# 12V_Supply.net
KiCad netlist of a schematic drawn in Altium Designer
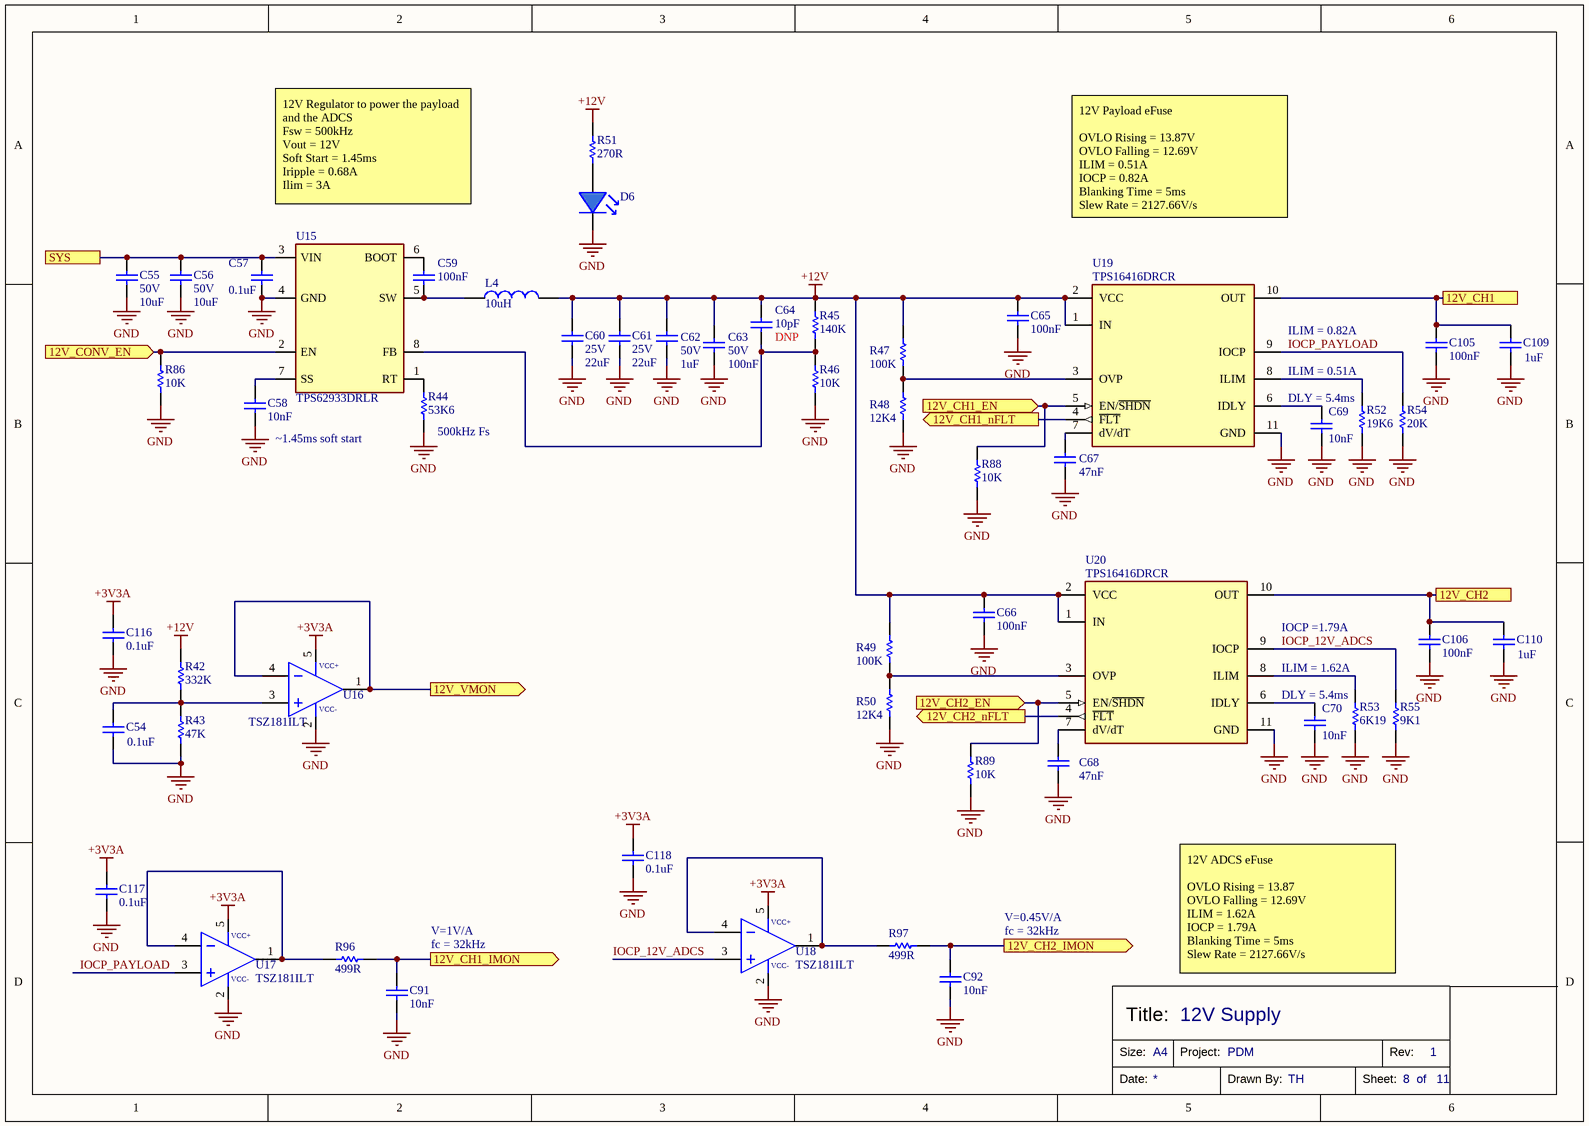
[diagram p0: 12V_Supply.SchDoc]

(export (version "E")
  (design (tool "Eeschema 10.0.6"))
  (components
    (comp (ref "C54")
      (value "CL21B104KACNNNC")
      (footprint "CAPC0805X060")
      (description "0.1uF ±10% 25V Ceramic Capacitor X7R 0805 (2012 Metric)")
      (fields
        (field (name "DISTRIBUTOR PART NUMBER") "1276-1099-1-ND")
        (field (name "TOLERANCE") "10%")
        (field (name "CAPACITANCE") "0.1uF")
      )
      (libsource (lib "Ahristi_Library") (part "CL21B104KACNNNC"))
    )
    (comp (ref "C55")
      (value "CL32B106KBJNNNE")
      (footprint "CAPC1210X090")
      (description "10 µF ±10% 50V Ceramic Capacitor X7R 1210 (3225 Metric)")
      (fields
        (field (name "DISTRIBUTOR PART NUMBER") "1276-3387-1-ND")
        (field (name "TOLERANCE") "10%")
        (field (name "VOLTAGE RATING") "50V")
        (field (name "CAPACITANCE") "10uF")
      )
      (libsource (lib "Ahristi_Library") (part "CL32B106KBJNNNE"))
    )
    (comp (ref "C56")
      (value "CL32B106KBJNNNE")
      (footprint "CAPC1210X090")
      (description "10 µF ±10% 50V Ceramic Capacitor X7R 1210 (3225 Metric)")
      (fields
        (field (name "DISTRIBUTOR PART NUMBER") "1276-3387-1-ND")
        (field (name "TOLERANCE") "10%")
        (field (name "VOLTAGE RATING") "50V")
        (field (name "CAPACITANCE") "10uF")
      )
      (libsource (lib "Ahristi_Library") (part "CL32B106KBJNNNE"))
    )
    (comp (ref "C57")
      (value "CL05B104KB5NNNC")
      (footprint "CAPC0402X020")
      (description "0.1 µF ±10% 50V Ceramic Capacitor X7R 0402 (1005 Metric)")
      (fields
        (field (name "TOLERANCE") "10%")
        (field (name "DISTRIBUTOR PART NUMBER") "1276-CL05B104KB5NNNCCT-ND")
        (field (name "CAPACITANCE") "0.1uF")
      )
      (libsource (lib "Ahristi_Library") (part "CL05B104KB5NNNC"))
    )
    (comp (ref "C58")
      (value "CL21B103KBANNNC")
      (footprint "CAPC0805X060")
      (description "10nF ±10% 50V Ceramic Capacitor X7R 0805 (2012 Metric)")
      (fields
        (field (name "DISTRIBUTOR PART NUMBER") "1276-1015-1-ND")
        (field (name "TOLERANCE") "10%")
        (field (name "CAPACITANCE") "10nF")
      )
      (libsource (lib "Ahristi_Library") (part "CL21B103KBANNNC"))
    )
    (comp (ref "C59")
      (value "C0603C104K5RACTU")
      (footprint "CAPC0603X040")
      (description "0.1 µF ±10% 50V Ceramic Capacitor X7R 0603 (1608 Metric)")
      (fields
        (field (name "DISTRIBUTOR PART NUMBER") "399-C0603C104K5RACTUCT-ND")
        (field (name "TOLERANCE") "10%")
        (field (name "CAPACITANCE") "100nF")
      )
      (libsource (lib "Ahristi_Library") (part "C0603C104K5RACTU"))
    )
    (comp (ref "C60")
      (value "CL32B226KAJNNNE")
      (footprint "CAPC1210X090")
      (description "22 µF ±10% 25V Ceramic Capacitor X7R 1210 (3225 Metric)")
      (fields
        (field (name "DISTRIBUTOR PART NUMBER") "1276-3392-1-ND")
        (field (name "TOLERANCE") "10%")
        (field (name "VOLTAGE RATING") "25V")
        (field (name "CAPACITANCE") "22uF")
      )
      (libsource (lib "Ahristi_Library") (part "CL32B226KAJNNNE"))
    )
    (comp (ref "C61")
      (value "CL32B226KAJNNNE")
      (footprint "CAPC1210X090")
      (description "22 µF ±10% 25V Ceramic Capacitor X7R 1210 (3225 Metric)")
      (fields
        (field (name "DISTRIBUTOR PART NUMBER") "1276-3392-1-ND")
        (field (name "TOLERANCE") "10%")
        (field (name "VOLTAGE RATING") "25V")
        (field (name "CAPACITANCE") "22uF")
      )
      (libsource (lib "Ahristi_Library") (part "CL32B226KAJNNNE"))
    )
    (comp (ref "C62")
      (value "CL21B105KBFNNNE")
      (footprint "CAPC0805X060")
      (description "1uF 50V X7R ±10% 0805 Multilayer Ceramic Capacitors MLCC - SMD/SMT ROHS")
      (fields
        (field (name "DISTRIBUTOR PART NUMBER") "1276-1029-1-ND")
        (field (name "TOLERANCE") "10%")
        (field (name "VOLTAGE RATING") "50V")
        (field (name "CAPACITANCE") "1uF")
      )
      (libsource (lib "Ahristi_Library") (part "CL21B105KBFNNNE"))
    )
    (comp (ref "C63")
      (value "C0603C104K5RACTU")
      (footprint "CAPC0603X040")
      (description "0.1 µF ±10% 50V Ceramic Capacitor X7R 0603 (1608 Metric)")
      (fields
        (field (name "DISTRIBUTOR PART NUMBER") "399-C0603C104K5RACTUCT-ND")
        (field (name "TOLERANCE") "10%")
        (field (name "VOLTAGE RATING") "50V")
        (field (name "CAPACITANCE") "100nF")
      )
      (libsource (lib "Ahristi_Library") (part "C0603C104K5RACTU"))
    )
    (comp (ref "C64")
      (value "C0603C104K5RACTU")
      (footprint "CAPC0603X040")
      (description "10 pF ±5% 50V Ceramic Capacitor C0G, NP0 0603 (1608 Metric)")
      (fields
        (field (name "PART NUMBER") "C0603C100J5GACTU")
        (field (name "DISTRIBUTOR PART NUMBER") "399-C0603C100J5GACTUCT-ND")
        (field (name "CAPACITANCE") "10pF")
      )
      (libsource (lib "Ahristi_Library") (part "C0603C100J5GACTU"))
    )
    (comp (ref "C65")
      (value "C0603C104K5RACTU")
      (footprint "CAPC0603X040")
      (description "0.1 µF ±10% 50V Ceramic Capacitor X7R 0603 (1608 Metric)")
      (fields
        (field (name "DISTRIBUTOR PART NUMBER") "399-C0603C104K5RACTUCT-ND")
        (field (name "TOLERANCE") "10%")
        (field (name "CAPACITANCE") "100nF")
      )
      (libsource (lib "Ahristi_Library") (part "C0603C104K5RACTU"))
    )
    (comp (ref "C66")
      (value "C0603C104K5RACTU")
      (footprint "CAPC0603X040")
      (description "0.1 µF ±10% 50V Ceramic Capacitor X7R 0603 (1608 Metric)")
      (fields
        (field (name "DISTRIBUTOR PART NUMBER") "399-C0603C104K5RACTUCT-ND")
        (field (name "TOLERANCE") "10%")
        (field (name "CAPACITANCE") "100nF")
      )
      (libsource (lib "Ahristi_Library") (part "C0603C104K5RACTU"))
    )
    (comp (ref "C67")
      (value "CL21B473KBCNNNC")
      (footprint "CAPC0805X060")
      (description "0.047 µF ±10% 50V Ceramic Capacitor X7R 0805 (2012 Metric)")
      (fields
        (field (name "DISTRIBUTOR PART NUMBER") "1276-1250-1-ND")
        (field (name "TOLERANCE") "10%")
        (field (name "CAPACITANCE") "47nF")
      )
      (libsource (lib "Ahristi_Library") (part "CL21B473KBCNNNC"))
    )
    (comp (ref "C68")
      (value "CL21B473KBCNNNC")
      (footprint "CAPC0805X060")
      (description "0.047 µF ±10% 50V Ceramic Capacitor X7R 0805 (2012 Metric)")
      (fields
        (field (name "DISTRIBUTOR PART NUMBER") "1276-1250-1-ND")
        (field (name "TOLERANCE") "10%")
        (field (name "CAPACITANCE") "47nF")
      )
      (libsource (lib "Ahristi_Library") (part "CL21B473KBCNNNC"))
    )
    (comp (ref "C69")
      (value "CL21B103KBANNNC")
      (footprint "CAPC0805X060")
      (description "10nF ±10% 50V Ceramic Capacitor X7R 0805 (2012 Metric)")
      (fields
        (field (name "DISTRIBUTOR PART NUMBER") "1276-1015-1-ND")
        (field (name "TOLERANCE") "10%")
        (field (name "CAPACITANCE") "10nF")
      )
      (libsource (lib "Ahristi_Library") (part "CL21B103KBANNNC"))
    )
    (comp (ref "C70")
      (value "CL21B103KBANNNC")
      (footprint "CAPC0805X060")
      (description "10nF ±10% 50V Ceramic Capacitor X7R 0805 (2012 Metric)")
      (fields
        (field (name "DISTRIBUTOR PART NUMBER") "1276-1015-1-ND")
        (field (name "TOLERANCE") "10%")
        (field (name "CAPACITANCE") "10nF")
      )
      (libsource (lib "Ahristi_Library") (part "CL21B103KBANNNC"))
    )
    (comp (ref "C91")
      (value "CL21B103KBANNNC")
      (footprint "CAPC0805X060")
      (description "10nF ±10% 50V Ceramic Capacitor X7R 0805 (2012 Metric)")
      (fields
        (field (name "DISTRIBUTOR PART NUMBER") "1276-1015-1-ND")
        (field (name "TOLERANCE") "10%")
        (field (name "CAPACITANCE") "10nF")
      )
      (libsource (lib "Ahristi_Library") (part "CL21B103KBANNNC"))
    )
    (comp (ref "C92")
      (value "CL21B103KBANNNC")
      (footprint "CAPC0805X060")
      (description "10nF ±10% 50V Ceramic Capacitor X7R 0805 (2012 Metric)")
      (fields
        (field (name "DISTRIBUTOR PART NUMBER") "1276-1015-1-ND")
        (field (name "TOLERANCE") "10%")
        (field (name "CAPACITANCE") "10nF")
      )
      (libsource (lib "Ahristi_Library") (part "CL21B103KBANNNC"))
    )
    (comp (ref "C105")
      (value "C0603C104K5RACTU")
      (footprint "CAPC0603X040")
      (description "0.1 µF ±10% 50V Ceramic Capacitor X7R 0603 (1608 Metric)")
      (fields
        (field (name "DISTRIBUTOR PART NUMBER") "399-C0603C104K5RACTUCT-ND")
        (field (name "TOLERANCE") "10%")
        (field (name "CAPACITANCE") "100nF")
      )
      (libsource (lib "Ahristi_Library") (part "C0603C104K5RACTU"))
    )
    (comp (ref "C106")
      (value "C0603C104K5RACTU")
      (footprint "CAPC0603X040")
      (description "0.1 µF ±10% 50V Ceramic Capacitor X7R 0603 (1608 Metric)")
      (fields
        (field (name "DISTRIBUTOR PART NUMBER") "399-C0603C104K5RACTUCT-ND")
        (field (name "TOLERANCE") "10%")
        (field (name "CAPACITANCE") "100nF")
      )
      (libsource (lib "Ahristi_Library") (part "C0603C104K5RACTU"))
    )
    (comp (ref "C109")
      (value "CL21B105KAFNNNE")
      (footprint "CAPC0805X060")
      (description "1uF ±10% 25V Ceramic Capacitor X7R 0805 (2012 Metric)")
      (fields
        (field (name "DISTRIBUTOR PART NUMBER") "1276-1066-1-ND")
        (field (name "TOLERANCE") "10%")
        (field (name "CAPACITANCE") "1uF")
      )
      (libsource (lib "Ahristi_Library") (part "CL21B105KAFNNNE"))
    )
    (comp (ref "C110")
      (value "CL21B105KAFNNNE")
      (footprint "CAPC0805X060")
      (description "1uF ±10% 25V Ceramic Capacitor X7R 0805 (2012 Metric)")
      (fields
        (field (name "DISTRIBUTOR PART NUMBER") "1276-1066-1-ND")
        (field (name "TOLERANCE") "10%")
        (field (name "CAPACITANCE") "1uF")
      )
      (libsource (lib "Ahristi_Library") (part "CL21B105KAFNNNE"))
    )
    (comp (ref "C116")
      (value "C0603C104K5RACTU")
      (footprint "CAPC0603X040")
      (description "0.1 µF ±10% 50V Ceramic Capacitor X7R 0603 (1608 Metric)")
      (fields
        (field (name "DISTRIBUTOR PART NUMBER") "399-C0603C104K5RACTUCT-ND")
        (field (name "TOLERANCE") "10%")
        (field (name "CAPACITANCE") "0.1uF")
      )
      (libsource (lib "Ahristi_Library") (part "C0603C104K5RACTU"))
    )
    (comp (ref "C117")
      (value "C0603C104K5RACTU")
      (footprint "CAPC0603X040")
      (description "0.1 µF ±10% 50V Ceramic Capacitor X7R 0603 (1608 Metric)")
      (fields
        (field (name "DISTRIBUTOR PART NUMBER") "399-C0603C104K5RACTUCT-ND")
        (field (name "TOLERANCE") "10%")
        (field (name "CAPACITANCE") "0.1uF")
      )
      (libsource (lib "Ahristi_Library") (part "C0603C104K5RACTU"))
    )
    (comp (ref "C118")
      (value "C0603C104K5RACTU")
      (footprint "CAPC0603X040")
      (description "0.1 µF ±10% 50V Ceramic Capacitor X7R 0603 (1608 Metric)")
      (fields
        (field (name "DISTRIBUTOR PART NUMBER") "399-C0603C104K5RACTUCT-ND")
        (field (name "TOLERANCE") "10%")
        (field (name "CAPACITANCE") "0.1uF")
      )
      (libsource (lib "Ahristi_Library") (part "C0603C104K5RACTU"))
    )
    (comp (ref "D6")
      (value "LSM0805463V")
      (footprint "LEDB_0805")
      (description "Blue 469nm LED Indication - Discrete 3V 0805 (2012 Metric)")
      (fields (field (name "DISTRIBUTOR PART NUMBER") "28-LSM0805463VCT-ND"))
      (libsource (lib "Ahristi_Library") (part "LEDB0805"))
    )
    (comp (ref "L4")
      (value "1274AS-H-100M=P3")
      (footprint "1274AS-H-100M=P3")
      (description "Inductor 10 µH , 4.4 A 30.4mOhm Max Shielded Drum Core")
      (fields (field (name "DISTRIBUTOR PART NUMBER") "490-10846-1-ND") (field (name "INDUCTANCE") "10uH"))
      (libsource (lib "Ahristi_Library") (part "1274AS-H-100M=P3"))
    )
    (comp (ref "R42")
      (value "RMCF0805FT332K")
      (footprint "RESC0805")
      (description "332 kOhms ±1% 0.125W, 1/8W Chip Resistor 0805 (2012 Metric) Automotive AEC-Q200 Thick Film")
      (fields
        (field (name "TOLERANCE") "1%")
        (field (name "DISTRIBUTOR PART NUMBER") "RMCF0805FT332KCT-ND")
        (field (name "RESISTANCE") "332K")
      )
      (libsource (lib "Ahristi_Library") (part "RMCF0805FT332K"))
    )
    (comp (ref "R43")
      (value "RMCF0805FT47K0")
      (footprint "RESC0805")
      (description "47 kOhms ±1% 0.125W, 1/8W Chip Resistor 0805 (2012 Metric) Automotive AEC-Q200 Thick Film")
      (fields
        (field (name "TOLERANCE") "1%")
        (field (name "DISTRIBUTOR PART NUMBER") "RMCF0805FT47K0CT-ND")
        (field (name "RESISTANCE") "47K")
      )
      (libsource (lib "Ahristi_Library") (part "RMCF0805FT47K0"))
    )
    (comp (ref "R44")
      (value "RMCF0805FT53K6")
      (footprint "RESC0805")
      (description "53.6 kOhms ±1% 0.125W, 1/8W Chip Resistor 0805 (2012 Metric) Automotive AEC-Q200 Thick Film")
      (fields
        (field (name "TOLERANCE") "1%")
        (field (name "DISTRIBUTOR PART NUMBER") "RMCF0805FT53K6CT-ND")
        (field (name "RESISTANCE") "53K6")
      )
      (libsource (lib "Ahristi_Library") (part "RMCF0805FT53K6"))
    )
    (comp (ref "R45")
      (value "RMCF0603FT140K")
      (footprint "RESC0603")
      (description "140 kOhms ±1% 0.1W, 1/10W Chip Resistor 0603 (1608 Metric) Automotive AEC-Q200 Thick Film")
      (fields
        (field (name "PART NUMBER") "RMCF0603FT100K")
        (field (name "TOLERANCE") "1%")
        (field (name "RESISTANCE") "140K")
      )
      (libsource (lib "Ahristi_Library") (part "RMCF0603FT140K"))
    )
    (comp (ref "R46")
      (value "RMCF0603FT10K0")
      (footprint "RESC0603")
      (description "10 kOhms ±1% 0.1W, 1/10W Chip Resistor 0603 (1608 Metric) Automotive AEC-Q200 Thick Film")
      (fields
        (field (name "TOLERANCE") "1%")
        (field (name "DISTRIBUTOR PART NUMBER") "RMCF0603FT10K0CT-ND")
        (field (name "RESISTANCE") "10K")
      )
      (libsource (lib "Ahristi_Library") (part "RMCF0603FT10K0"))
    )
    (comp (ref "R47")
      (value "RMCF0805FG100K")
      (footprint "RESC0805")
      (description "100 kOhms ±1% 0.125W, 1/8W Chip Resistor 0805 (2012 Metric) Automotive AEC-Q200 Thick Film")
      (fields
        (field (name "TOLERANCE") "1%")
        (field (name "DISTRIBUTOR PART NUMBER") "RMCF0805FG100KCT-ND")
        (field (name "RESISTANCE") "100K")
      )
      (libsource (lib "Ahristi_Library") (part "RMCF0805FG100K"))
    )
    (comp (ref "R48")
      (value "RMCF0805FT12K4")
      (footprint "RESC0805")
      (description "12.4 kOhms ±1% 0.125W, 1/8W Chip Resistor 0805 (2012 Metric) Automotive AEC-Q200 Thick Film")
      (fields
        (field (name "TOLERANCE") "1%")
        (field (name "DISTRIBUTOR PART NUMBER") "RMCF0805FT12K4CT-ND")
        (field (name "RESISTANCE") "12K4")
      )
      (libsource (lib "Ahristi_Library") (part "RMCF0805FT12K4"))
    )
    (comp (ref "R49")
      (value "RMCF0805FG100K")
      (footprint "RESC0805")
      (description "100 kOhms ±1% 0.125W, 1/8W Chip Resistor 0805 (2012 Metric) Automotive AEC-Q200 Thick Film")
      (fields
        (field (name "TOLERANCE") "1%")
        (field (name "DISTRIBUTOR PART NUMBER") "RMCF0805FG100KCT-ND")
        (field (name "RESISTANCE") "100K")
      )
      (libsource (lib "Ahristi_Library") (part "RMCF0805FG100K"))
    )
    (comp (ref "R50")
      (value "RMCF0805FT12K4")
      (footprint "RESC0805")
      (description "12.4 kOhms ±1% 0.125W, 1/8W Chip Resistor 0805 (2012 Metric) Automotive AEC-Q200 Thick Film")
      (fields
        (field (name "TOLERANCE") "1%")
        (field (name "DISTRIBUTOR PART NUMBER") "RMCF0805FT12K4CT-ND")
        (field (name "RESISTANCE") "12K4")
      )
      (libsource (lib "Ahristi_Library") (part "RMCF0805FT12K4"))
    )
    (comp (ref "R51")
      (value "RMCF0805FT270R")
      (footprint "RESC0805")
      (description "270 Ohms ±1% 0.125W, 1/8W Chip Resistor 0805 (2012 Metric) Automotive AEC-Q200 Thick Film")
      (fields
        (field (name "TOLERANCE") "1%")
        (field (name "DISTRIBUTOR PART NUMBER") "RMCF0805FT270RCT-ND")
        (field (name "RESISTANCE") "270R")
      )
      (libsource (lib "Ahristi_Library") (part "RMCF0805FT270R"))
    )
    (comp (ref "R52")
      (value "RMCF0805FT19K6")
      (footprint "RESC0805")
      (description "19.6 kOhms ±1% 0.125W, 1/8W Chip Resistor 0805 (2012 Metric) Automotive AEC-Q200 Thick Film")
      (fields
        (field (name "TOLERANCE") "1%")
        (field (name "DISTRIBUTOR PART NUMBER") "RMCF0805FT19K6CT-ND")
        (field (name "RESISTANCE") "19K6")
      )
      (libsource (lib "Ahristi_Library") (part "RMCF0805FT19K6"))
    )
    (comp (ref "R53")
      (value "RMCF0805FT6K19")
      (footprint "RESC0805")
      (description "6.19 kOhms ±1% 0.125W, 1/8W Chip Resistor 0805 (2012 Metric) Automotive AEC-Q200 Thick Film")
      (fields
        (field (name "TOLERANCE") "1%")
        (field (name "DISTRIBUTOR PART NUMBER") "RMCF0805FT6K19CT-ND")
        (field (name "RESISTANCE") "6K19")
      )
      (libsource (lib "Ahristi_Library") (part "RMCF0805FT6K19"))
    )
    (comp (ref "R54")
      (value "RMCF0805FT20K0")
      (footprint "RESC0805")
      (description "20 kOhms ±1% 0.125W, 1/8W Chip Resistor 0805 (2012 Metric) Automotive AEC-Q200 Thick Film")
      (fields
        (field (name "TOLERANCE") "1%")
        (field (name "DISTRIBUTOR PART NUMBER") "RMCF0805FT20K0CT-ND")
        (field (name "RESISTANCE") "20K")
      )
      (libsource (lib "Ahristi_Library") (part "RMCF0805FT20K0"))
    )
    (comp (ref "R55")
      (value "RMCF0805FT9K10")
      (footprint "RESC0805")
      (description "9.1 kOhms ±1% 0.125W, 1/8W Chip Resistor 0805 (2012 Metric) Automotive AEC-Q200 Thick Film")
      (fields
        (field (name "TOLERANCE") "1%")
        (field (name "DISTRIBUTOR PART NUMBER") "738-RMCF0805FT9K10CT-ND")
        (field (name "RESISTANCE") "9K1")
      )
      (libsource (lib "Ahristi_Library") (part "RMCF0805FT9K10"))
    )
    (comp (ref "R86")
      (value "RMCF0805FT10K0")
      (footprint "RESC0805")
      (description "10 kOhms ±1% 0.125W, 1/8W Chip Resistor 0805 (2012 Metric) Automotive AEC-Q200 Thick Film")
      (fields
        (field (name "TOLERANCE") "1%")
        (field (name "DISTRIBUTOR PART NUMBER") "RMCF0805FT10K0CT-ND")
        (field (name "RESISTANCE") "10K")
      )
      (libsource (lib "Ahristi_Library") (part "RMCF0805FT10K0"))
    )
    (comp (ref "R88")
      (value "RMCF0805FT10K0")
      (footprint "RESC0805")
      (description "10 kOhms ±1% 0.125W, 1/8W Chip Resistor 0805 (2012 Metric) Automotive AEC-Q200 Thick Film")
      (fields
        (field (name "TOLERANCE") "1%")
        (field (name "DISTRIBUTOR PART NUMBER") "RMCF0805FT10K0CT-ND")
        (field (name "RESISTANCE") "10K")
      )
      (libsource (lib "Ahristi_Library") (part "RMCF0805FT10K0"))
    )
    (comp (ref "R89")
      (value "RMCF0805FT10K0")
      (footprint "RESC0805")
      (description "10 kOhms ±1% 0.125W, 1/8W Chip Resistor 0805 (2012 Metric) Automotive AEC-Q200 Thick Film")
      (fields
        (field (name "TOLERANCE") "1%")
        (field (name "DISTRIBUTOR PART NUMBER") "RMCF0805FT10K0CT-ND")
        (field (name "RESISTANCE") "10K")
      )
      (libsource (lib "Ahristi_Library") (part "RMCF0805FT10K0"))
    )
    (comp (ref "R96")
      (value "RMCF0805FT499R")
      (footprint "RESC0805")
      (description "499 Ohms ±1% 0.125W, 1/8W Chip Resistor 0805 (2012 Metric) Automotive AEC-Q200 Thick Film")
      (fields
        (field (name "TOLERANCE") "1%")
        (field (name "DISTRIBUTOR PART NUMBER") "RMCF0805FT499RCT-ND")
        (field (name "RESISTANCE") "499R")
      )
      (libsource (lib "Ahristi_Library") (part "RMCF0805FT499R"))
    )
    (comp (ref "R97")
      (value "RMCF0805FT499R")
      (footprint "RESC0805")
      (description "499 Ohms ±1% 0.125W, 1/8W Chip Resistor 0805 (2012 Metric) Automotive AEC-Q200 Thick Film")
      (fields
        (field (name "TOLERANCE") "1%")
        (field (name "DISTRIBUTOR PART NUMBER") "RMCF0805FT499RCT-ND")
        (field (name "RESISTANCE") "499R")
      )
      (libsource (lib "Ahristi_Library") (part "RMCF0805FT499R"))
    )
    (comp (ref "U15")
      (value "TPS62933DRLR")
      (footprint "SOT-583")
      (description "Buck Switching Regulator IC Positive Adjustable 0.8V 1 Output 3A SOT-583")
      (fields (field (name "DISTRIBUTOR PART NUMBER") "296-TPS62933DRLRCT-ND"))
      (libsource (lib "Ahristi_Library") (part "TPS62933DRLR"))
    )
    (comp (ref "U16")
      (value "TSZ181ILT")
      (footprint "SOT23-5 IC")
      (description "Operational Amplifier, General Purpose, 2.2V~5.5V")
      (fields (field (name "DISTRIBUTOR PART NUMBER") "497-18084-1-ND"))
      (libsource (lib "Ahristi_Library") (part "TSZ181ILT"))
    )
    (comp (ref "U17")
      (value "TSZ181ILT")
      (footprint "SOT23-5 IC")
      (description "Operational Amplifier, General Purpose, 2.2V~5.5V")
      (fields (field (name "DISTRIBUTOR PART NUMBER") "497-18084-1-ND"))
      (libsource (lib "Ahristi_Library") (part "TSZ181ILT"))
    )
    (comp (ref "U18")
      (value "TSZ181ILT")
      (footprint "SOT23-5 IC")
      (description "Operational Amplifier, General Purpose, 2.2V~5.5V")
      (fields (field (name "DISTRIBUTOR PART NUMBER") "497-18084-1-ND"))
      (libsource (lib "Ahristi_Library") (part "TSZ181ILT"))
    )
    (comp (ref "U19")
      (value "TPS16410DRCR")
      (footprint "TPS1641")
      (description "2.7-V to 40-V 152-mΩ 1.8-A eFuse with output power limiting")
      (fields
        (field (name "DISTRIBUTOR PART NUMBER") "296-TPS16410DRCRCT-ND")
        (field (name "PART NUMBER") "TPS16416DRCR")
      )
      (libsource (lib "Ahristi_Library") (part "TPS16410DRCR"))
    )
    (comp (ref "U20")
      (value "TPS16410DRCR")
      (footprint "TPS1641")
      (description "2.7-V to 40-V 152-mΩ 1.8-A eFuse with output power limiting")
      (fields
        (field (name "DISTRIBUTOR PART NUMBER") "296-TPS16410DRCRCT-ND")
        (field (name "PART NUMBER") "TPS16416DRCR")
      )
      (libsource (lib "Ahristi_Library") (part "TPS16410DRCR"))
    )
  )
  (nets
    (net (code "1") (name "+3V3A") (class "Default")
      (node (ref "C116") (pin "2") (pinfunction "2_2") (pintype "passive"))
      (node (ref "C117") (pin "2") (pinfunction "2_2") (pintype "passive"))
      (node (ref "C118") (pin "2") (pinfunction "2_2") (pintype "passive"))
      (node (ref "U16") (pin "5") (pinfunction "VCC+_5") (pintype "power_in"))
      (node (ref "U17") (pin "5") (pinfunction "VCC+_5") (pintype "power_in"))
      (node (ref "U18") (pin "5") (pinfunction "VCC+_5") (pintype "power_in"))
    )
    (net (code "2") (name "+12V") (class "Default")
      (node (ref "C60") (pin "2") (pinfunction "2_2") (pintype "passive"))
      (node (ref "C61") (pin "2") (pinfunction "2_2") (pintype "passive"))
      (node (ref "C62") (pin "2") (pinfunction "2_2") (pintype "passive"))
      (node (ref "C63") (pin "2") (pinfunction "2_2") (pintype "passive"))
      (node (ref "C64") (pin "2") (pinfunction "2_2") (pintype "passive"))
      (node (ref "C65") (pin "2") (pinfunction "2_2") (pintype "passive"))
      (node (ref "C66") (pin "2") (pinfunction "2_2") (pintype "passive"))
      (node (ref "L4") (pin "2") (pinfunction "2_2") (pintype "passive"))
      (node (ref "R42") (pin "2") (pinfunction "2_2") (pintype "passive"))
      (node (ref "R45") (pin "2") (pinfunction "2_2") (pintype "passive"))
      (node (ref "R47") (pin "2") (pinfunction "2_2") (pintype "passive"))
      (node (ref "R49") (pin "2") (pinfunction "2_2") (pintype "passive"))
      (node (ref "R51") (pin "2") (pinfunction "2_2") (pintype "passive"))
      (node (ref "U19") (pin "1") (pinfunction "IN_1") (pintype "passive"))
      (node (ref "U19") (pin "2") (pinfunction "VCC_2") (pintype "passive"))
      (node (ref "U20") (pin "1") (pinfunction "IN_1") (pintype "passive"))
      (node (ref "U20") (pin "2") (pinfunction "VCC_2") (pintype "passive"))
    )
    (net (code "3") (name "/12V_CH1") (class "Default")
      (node (ref "C105") (pin "2") (pinfunction "2_2") (pintype "passive"))
      (node (ref "C109") (pin "2") (pinfunction "2_2") (pintype "passive"))
      (node (ref "U19") (pin "10") (pinfunction "OUT_10") (pintype "passive"))
    )
    (net (code "4") (name "/12V_CH1_EN") (class "Default")
      (node (ref "R88") (pin "2") (pinfunction "2_2") (pintype "passive"))
      (node (ref "U19") (pin "5") (pinfunction "EN/~{SHDN}_5") (pintype "input"))
    )
    (net (code "5") (name "/12V_CH1_IMON") (class "Default")
      (node (ref "C91") (pin "2") (pinfunction "2_2") (pintype "passive"))
      (node (ref "R96") (pin "2") (pinfunction "2_2") (pintype "passive"))
    )
    (net (code "6") (name "/12V_CH1_nFLT") (class "Default")
      (node (ref "U19") (pin "4") (pinfunction "~{FLT}_4") (pintype "output"))
    )
    (net (code "7") (name "/12V_CH2") (class "Default")
      (node (ref "C106") (pin "2") (pinfunction "2_2") (pintype "passive"))
      (node (ref "C110") (pin "2") (pinfunction "2_2") (pintype "passive"))
      (node (ref "U20") (pin "10") (pinfunction "OUT_10") (pintype "passive"))
    )
    (net (code "8") (name "/12V_CH2_EN") (class "Default")
      (node (ref "R89") (pin "2") (pinfunction "2_2") (pintype "passive"))
      (node (ref "U20") (pin "5") (pinfunction "EN/~{SHDN}_5") (pintype "input"))
    )
    (net (code "9") (name "/12V_CH2_IMON") (class "Default")
      (node (ref "C92") (pin "2") (pinfunction "2_2") (pintype "passive"))
      (node (ref "R97") (pin "2") (pinfunction "2_2") (pintype "passive"))
    )
    (net (code "10") (name "/12V_CH2_nFLT") (class "Default")
      (node (ref "U20") (pin "4") (pinfunction "~{FLT}_4") (pintype "output"))
    )
    (net (code "11") (name "/12V_CONV_EN") (class "Default")
      (node (ref "R86") (pin "2") (pinfunction "2_2") (pintype "passive"))
      (node (ref "U15") (pin "2") (pinfunction "EN_2") (pintype "passive"))
    )
    (net (code "12") (name "/12V_VMON") (class "Default")
      (node (ref "U16") (pin "1") (pinfunction "OUT_1") (pintype "passive"))
      (node (ref "U16") (pin "4") (pinfunction "IN-_4") (pintype "passive"))
    )
    (net (code "13") (name "/IOCP_12V_ADCS") (class "Default")
      (node (ref "R55") (pin "2") (pinfunction "2_2") (pintype "passive"))
      (node (ref "U18") (pin "3") (pinfunction "IN+_3") (pintype "passive"))
      (node (ref "U20") (pin "9") (pinfunction "IOCP_9") (pintype "passive"))
    )
    (net (code "14") (name "/IOCP_PAYLOAD") (class "Default")
      (node (ref "R54") (pin "2") (pinfunction "2_2") (pintype "passive"))
      (node (ref "U17") (pin "3") (pinfunction "IN+_3") (pintype "passive"))
      (node (ref "U19") (pin "9") (pinfunction "IOCP_9") (pintype "passive"))
    )
    (net (code "15") (name "/SYS") (class "Default")
      (node (ref "C55") (pin "2") (pinfunction "2_2") (pintype "passive"))
      (node (ref "C56") (pin "2") (pinfunction "2_2") (pintype "passive"))
      (node (ref "C57") (pin "2") (pinfunction "2_2") (pintype "passive"))
      (node (ref "U15") (pin "3") (pinfunction "VIN_3") (pintype "passive"))
    )
    (net (code "16") (name "GND") (class "Default")
      (node (ref "C105") (pin "1") (pinfunction "1_1") (pintype "passive"))
      (node (ref "C106") (pin "1") (pinfunction "1_1") (pintype "passive"))
      (node (ref "C109") (pin "1") (pinfunction "1_1") (pintype "passive"))
      (node (ref "C110") (pin "1") (pinfunction "1_1") (pintype "passive"))
      (node (ref "C116") (pin "1") (pinfunction "1_1") (pintype "passive"))
      (node (ref "C117") (pin "1") (pinfunction "1_1") (pintype "passive"))
      (node (ref "C118") (pin "1") (pinfunction "1_1") (pintype "passive"))
      (node (ref "C54") (pin "1") (pinfunction "1_1") (pintype "passive"))
      (node (ref "C55") (pin "1") (pinfunction "1_1") (pintype "passive"))
      (node (ref "C56") (pin "1") (pinfunction "1_1") (pintype "passive"))
      (node (ref "C57") (pin "1") (pinfunction "1_1") (pintype "passive"))
      (node (ref "C58") (pin "1") (pinfunction "1_1") (pintype "passive"))
      (node (ref "C60") (pin "1") (pinfunction "1_1") (pintype "passive"))
      (node (ref "C61") (pin "1") (pinfunction "1_1") (pintype "passive"))
      (node (ref "C62") (pin "1") (pinfunction "1_1") (pintype "passive"))
      (node (ref "C63") (pin "1") (pinfunction "1_1") (pintype "passive"))
      (node (ref "C65") (pin "1") (pinfunction "1_1") (pintype "passive"))
      (node (ref "C66") (pin "1") (pinfunction "1_1") (pintype "passive"))
      (node (ref "C67") (pin "1") (pinfunction "1_1") (pintype "passive"))
      (node (ref "C68") (pin "1") (pinfunction "1_1") (pintype "passive"))
      (node (ref "C69") (pin "1") (pinfunction "1_1") (pintype "passive"))
      (node (ref "C70") (pin "1") (pinfunction "1_1") (pintype "passive"))
      (node (ref "C91") (pin "1") (pinfunction "1_1") (pintype "passive"))
      (node (ref "C92") (pin "1") (pinfunction "1_1") (pintype "passive"))
      (node (ref "D6") (pin "K") (pinfunction "K_K") (pintype "passive"))
      (node (ref "R43") (pin "1") (pinfunction "1_1") (pintype "passive"))
      (node (ref "R44") (pin "1") (pinfunction "1_1") (pintype "passive"))
      (node (ref "R46") (pin "1") (pinfunction "1_1") (pintype "passive"))
      (node (ref "R48") (pin "1") (pinfunction "1_1") (pintype "passive"))
      (node (ref "R50") (pin "1") (pinfunction "1_1") (pintype "passive"))
      (node (ref "R52") (pin "1") (pinfunction "1_1") (pintype "passive"))
      (node (ref "R53") (pin "1") (pinfunction "1_1") (pintype "passive"))
      (node (ref "R54") (pin "1") (pinfunction "1_1") (pintype "passive"))
      (node (ref "R55") (pin "1") (pinfunction "1_1") (pintype "passive"))
      (node (ref "R86") (pin "1") (pinfunction "1_1") (pintype "passive"))
      (node (ref "R88") (pin "1") (pinfunction "1_1") (pintype "passive"))
      (node (ref "R89") (pin "1") (pinfunction "1_1") (pintype "passive"))
      (node (ref "U15") (pin "4") (pinfunction "GND_4") (pintype "passive"))
      (node (ref "U16") (pin "2") (pinfunction "VCC-_2") (pintype "power_in"))
      (node (ref "U17") (pin "2") (pinfunction "VCC-_2") (pintype "power_in"))
      (node (ref "U18") (pin "2") (pinfunction "VCC-_2") (pintype "power_in"))
      (node (ref "U19") (pin "11") (pinfunction "GND_11") (pintype "passive"))
      (node (ref "U20") (pin "11") (pinfunction "GND_11") (pintype "passive"))
    )
    (net (code "17") (name "Net-(D6-PadA)") (class "Default")
      (node (ref "D6") (pin "A") (pinfunction "A_A") (pintype "passive"))
      (node (ref "R51") (pin "1") (pinfunction "1_1") (pintype "passive"))
    )
    (net (code "18") (name "Net-(U15-BOOT)") (class "Default")
      (node (ref "C59") (pin "2") (pinfunction "2_2") (pintype "passive"))
      (node (ref "U15") (pin "6") (pinfunction "BOOT_6") (pintype "passive"))
    )
    (net (code "19") (name "Net-(U15-FB)") (class "Default")
      (node (ref "C64") (pin "1") (pinfunction "1_1") (pintype "passive"))
      (node (ref "R45") (pin "1") (pinfunction "1_1") (pintype "passive"))
      (node (ref "R46") (pin "2") (pinfunction "2_2") (pintype "passive"))
      (node (ref "U15") (pin "8") (pinfunction "FB_8") (pintype "passive"))
    )
    (net (code "20") (name "Net-(U15-RT)") (class "Default")
      (node (ref "R44") (pin "2") (pinfunction "2_2") (pintype "passive"))
      (node (ref "U15") (pin "1") (pinfunction "RT_1") (pintype "passive"))
    )
    (net (code "21") (name "Net-(U15-SS)") (class "Default")
      (node (ref "C58") (pin "2") (pinfunction "2_2") (pintype "passive"))
      (node (ref "U15") (pin "7") (pinfunction "SS_7") (pintype "passive"))
    )
    (net (code "22") (name "Net-(U15-SW)") (class "Default")
      (node (ref "C59") (pin "1") (pinfunction "1_1") (pintype "passive"))
      (node (ref "L4") (pin "1") (pinfunction "1_1") (pintype "passive"))
      (node (ref "U15") (pin "5") (pinfunction "SW_5") (pintype "passive"))
    )
    (net (code "23") (name "Net-(U16-IN+)") (class "Default")
      (node (ref "C54") (pin "2") (pinfunction "2_2") (pintype "passive"))
      (node (ref "R42") (pin "1") (pinfunction "1_1") (pintype "passive"))
      (node (ref "R43") (pin "2") (pinfunction "2_2") (pintype "passive"))
      (node (ref "U16") (pin "3") (pinfunction "IN+_3") (pintype "passive"))
    )
    (net (code "24") (name "Net-(U17-IN-)") (class "Default")
      (node (ref "R96") (pin "1") (pinfunction "1_1") (pintype "passive"))
      (node (ref "U17") (pin "1") (pinfunction "OUT_1") (pintype "passive"))
      (node (ref "U17") (pin "4") (pinfunction "IN-_4") (pintype "passive"))
    )
    (net (code "25") (name "Net-(U18-IN-)") (class "Default")
      (node (ref "R97") (pin "1") (pinfunction "1_1") (pintype "passive"))
      (node (ref "U18") (pin "1") (pinfunction "OUT_1") (pintype "passive"))
      (node (ref "U18") (pin "4") (pinfunction "IN-_4") (pintype "passive"))
    )
    (net (code "26") (name "Net-(U19-IDLY)") (class "Default")
      (node (ref "C69") (pin "2") (pinfunction "2_2") (pintype "passive"))
      (node (ref "U19") (pin "6") (pinfunction "IDLY_6") (pintype "passive"))
    )
    (net (code "27") (name "Net-(U19-ILIM)") (class "Default")
      (node (ref "R52") (pin "2") (pinfunction "2_2") (pintype "passive"))
      (node (ref "U19") (pin "8") (pinfunction "ILIM_8") (pintype "passive"))
    )
    (net (code "28") (name "Net-(U19-OVP)") (class "Default")
      (node (ref "R47") (pin "1") (pinfunction "1_1") (pintype "passive"))
      (node (ref "R48") (pin "2") (pinfunction "2_2") (pintype "passive"))
      (node (ref "U19") (pin "3") (pinfunction "OVP_3") (pintype "passive"))
    )
    (net (code "29") (name "Net-(U19-dV{slash}dT)") (class "Default")
      (node (ref "C67") (pin "2") (pinfunction "2_2") (pintype "passive"))
      (node (ref "U19") (pin "7") (pinfunction "dV/dT_7") (pintype "passive"))
    )
    (net (code "30") (name "Net-(U20-IDLY)") (class "Default")
      (node (ref "C70") (pin "2") (pinfunction "2_2") (pintype "passive"))
      (node (ref "U20") (pin "6") (pinfunction "IDLY_6") (pintype "passive"))
    )
    (net (code "31") (name "Net-(U20-ILIM)") (class "Default")
      (node (ref "R53") (pin "2") (pinfunction "2_2") (pintype "passive"))
      (node (ref "U20") (pin "8") (pinfunction "ILIM_8") (pintype "passive"))
    )
    (net (code "32") (name "Net-(U20-OVP)") (class "Default")
      (node (ref "R49") (pin "1") (pinfunction "1_1") (pintype "passive"))
      (node (ref "R50") (pin "2") (pinfunction "2_2") (pintype "passive"))
      (node (ref "U20") (pin "3") (pinfunction "OVP_3") (pintype "passive"))
    )
    (net (code "33") (name "Net-(U20-dV{slash}dT)") (class "Default")
      (node (ref "C68") (pin "2") (pinfunction "2_2") (pintype "passive"))
      (node (ref "U20") (pin "7") (pinfunction "dV/dT_7") (pintype "passive"))
    )
  )
)
